# MCU.net
KiCad netlist of a schematic drawn in Altium Designer
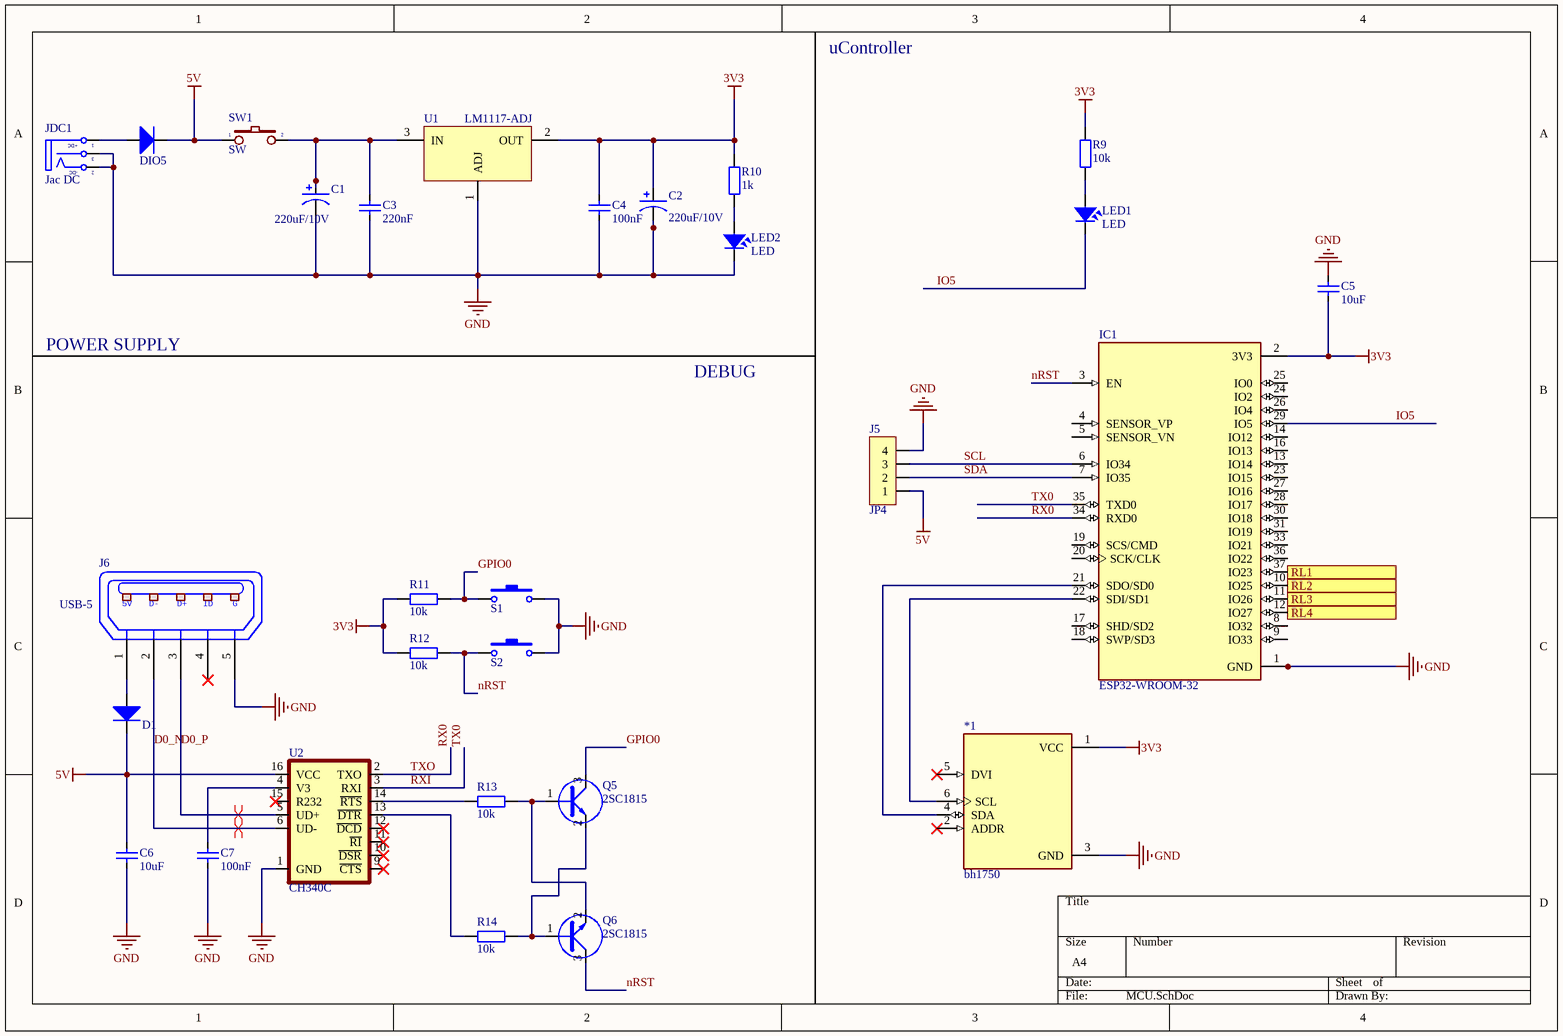
[diagram p0: MCU.SchDoc]

(export (version "E")
  (design (tool "Eeschema 10.0.6"))
  (components
    (comp (ref "*1") (value "bh1750") (footprint "BH1750") (libsource (lib "Main") (part "bh1750")))
    (comp (ref "C1")
      (value "220uF/10V")
      (footprint "C5mm")
      (description "Polarized Capacitor (Axial)")
      (fields (field (name "PUBLISHER") "Altium Limited"))
      (libsource (lib "Ven_lib") (part "Cap Pol"))
    )
    (comp (ref "C2")
      (value "220uF/10V")
      (footprint "C5mm")
      (description "Polarized Capacitor (Axial)")
      (fields (field (name "PUBLISHER") "Altium Limited"))
      (libsource (lib "Ven_lib") (part "Cap Pol"))
    )
    (comp (ref "C3")
      (value "220nF")
      (footprint "CAP_0805")
      (description "Capacitor")
      (fields (field (name "PUBLISHER") "Altium Limited"))
      (libsource (lib "My Library") (part "CapSMD"))
    )
    (comp (ref "C4")
      (value "100nF")
      (footprint "CAP_0805")
      (description "Capacitor")
      (fields (field (name "PUBLISHER") "Altium Limited"))
      (libsource (lib "My Library") (part "CapSMD"))
    )
    (comp (ref "C5")
      (value "10uF")
      (footprint "CAP_0805")
      (description "Capacitor")
      (fields (field (name "PUBLISHER") "Altium Limited"))
      (libsource (lib "My Library") (part "CapSMD"))
    )
    (comp (ref "C6")
      (value "10uF")
      (footprint "CAP_0805")
      (description "Capacitor")
      (fields (field (name "PUBLISHER") "Altium Limited"))
      (libsource (lib "My Library") (part "CapSMD"))
    )
    (comp (ref "C7")
      (value "100nF")
      (footprint "CAP_0805")
      (description "Capacitor")
      (fields (field (name "PUBLISHER") "Altium Limited"))
      (libsource (lib "My Library") (part "CapSMD"))
    )
    (comp (ref "D1")
      (value "Diode SMD")
      (footprint "DIO-214AC(SMA)")
      (description "Default Diode")
      (fields (field (name "PUBLISHER") "Altium Limited"))
      (libsource (lib "My Library") (part "Diode SMD"))
    )
    (comp (ref "DIO5")
      (value "Diode SMD")
      (footprint "DIO-214AC(SMA)")
      (description "Default Diode")
      (fields (field (name "PUBLISHER") "Altium Limited"))
      (libsource (lib "My Library") (part "Diode SMD"))
    )
    (comp (ref "IC1")
      (value "ESP32-WROOM-32")
      (footprint "MODULE_ESP32-WROOM-32")
      (description "Bluetooth, WiFi Transceiver Module 2.4GHz ~ 2.5GHz Surface Mount")
      (fields (field (name "MF") "Espressif Systems") (field (name "DIGI-KEY_PART_NUMBER") "1904-1010-1-ND"))
      (libsource (lib "Ven_lib") (part "ESP32-WROOM-32"))
    )
    (comp (ref "J5")
      (value "JP4")
      (footprint "JP4-C1T")
      (description "WR-PHD 2.54 mm Angled Socket Header")
      (fields
        (field (name "MANUFACTURER") "Würth Elektronik eiSos GmbH")
        (field (name "PARTNO") "613004143121")
        (field (name "CREATED BY") "Karrer Zheng")
      )
      (libsource (lib "My Library") (part "JP4"))
    )
    (comp (ref "J6")
      (value "USB-5")
      (footprint "USB-M1")
      (fields
        (field (name "MANUFACTURER") "FCI")
        (field (name "MANUFACTURER PART NUMBER") "10118193-0001LF")
        (field (name ".CREATOR") "MM")
        (field (name ".CHECKED PCB") "RF")
        (field (name ".CHECKED SCH") "MM")
      )
      (libsource (lib "My Library") (part "USB-5"))
    )
    (comp (ref "JDC1")
      (value "Jac DC")
      (footprint "DC-IN")
      (description "Jac DC input")
      (libsource (lib "My Library") (part "DCIN"))
    )
    (comp (ref "LED1")
      (value "LED")
      (footprint "LED-0805-Orange")
      (description "LED Single colour Green and Red")
      (libsource (lib "My Library") (part "LED"))
    )
    (comp (ref "LED2")
      (value "LED")
      (footprint "LED-0805-Red")
      (description "LED Single colour Green and Red")
      (libsource (lib "My Library") (part "LED"))
    )
    (comp (ref "Q5")
      (value "2SC1815")
      (footprint "SOT23D")
      (description "NPN 600mW, ECB")
      (libsource (lib "My Library") (part "C1815"))
    )
    (comp (ref "Q6")
      (value "2SC1815")
      (footprint "SOT23D")
      (description "NPN 600mW, ECB")
      (libsource (lib "") (part "C1815_1"))
    )
    (comp (ref "R9")
      (value "10k")
      (footprint "RES-SMD-0805")
      (description "Resistor SMD")
      (fields
        (field (name "MANUFACTURER") "Generic Components")
        (field (name "PUBLISHER") "Altium Hobart Technology Centre")
      )
      (libsource (lib "My Library") (part "Resistor - SMD"))
    )
    (comp (ref "R10")
      (value "1k")
      (footprint "RES-SMD-0805")
      (description "Resistor SMD")
      (fields
        (field (name "MANUFACTURER") "Generic Components")
        (field (name "PUBLISHER") "Altium Hobart Technology Centre")
      )
      (libsource (lib "My Library") (part "Resistor - SMD"))
    )
    (comp (ref "R11")
      (value "10k")
      (footprint "RES-SMD-0805")
      (description "Resistor SMD")
      (fields
        (field (name "MANUFACTURER") "Generic Components")
        (field (name "PUBLISHER") "Altium Hobart Technology Centre")
      )
      (libsource (lib "My Library") (part "Resistor - SMD"))
    )
    (comp (ref "R12")
      (value "10k")
      (footprint "RES-SMD-0805")
      (description "Resistor SMD")
      (fields
        (field (name "MANUFACTURER") "Generic Components")
        (field (name "PUBLISHER") "Altium Hobart Technology Centre")
      )
      (libsource (lib "My Library") (part "Resistor - SMD"))
    )
    (comp (ref "R13")
      (value "10k")
      (footprint "RES-SMD-0805")
      (description "Resistor SMD")
      (fields
        (field (name "MANUFACTURER") "Generic Components")
        (field (name "PUBLISHER") "Altium Hobart Technology Centre")
      )
      (libsource (lib "My Library") (part "Resistor - SMD"))
    )
    (comp (ref "R14")
      (value "10k")
      (footprint "RES-SMD-0805")
      (description "Resistor SMD")
      (fields
        (field (name "MANUFACTURER") "Generic Components")
        (field (name "PUBLISHER") "Altium Hobart Technology Centre")
      )
      (libsource (lib "My Library") (part "Resistor - SMD"))
    )
    (comp (ref "S1")
      (value "SW-SMD")
      (footprint "SW 3x2x4")
      (description "Switch")
      (fields (field (name "PUBLISHER") "Altium Limited"))
      (libsource (lib "My Library") (part "SW-SMD"))
    )
    (comp (ref "S2")
      (value "SW-SMD")
      (footprint "SW 3x2x4")
      (description "Switch")
      (fields (field (name "PUBLISHER") "Altium Limited"))
      (libsource (lib "My Library") (part "SW-SMD"))
    )
    (comp (ref "SW1")
      (value "SW")
      (footprint "SW2")
      (description "Switch button 2 pin")
      (libsource (lib "My Library") (part "SW2"))
    )
    (comp (ref "U1")
      (value "LM1117-ADJ")
      (footprint "LM1117-SOP")
      (description "800mA Low-Dropout Linear Regulator")
      (fields (field (name "CREATOR") "Nguyen Ba Bien"))
      (libsource (lib "My Library") (part "LM1117-ADJ"))
    )
    (comp (ref "U2")
      (value "CH340C")
      (footprint "SOP-16")
      (description "USB to serial chip CH340")
      (fields (field (name "MF") "WCH"))
      (libsource (lib "My Library") (part "CH340C"))
    )
  )
  (nets
    (net (code "1") (name "/D0_N") (class "Default")
      (node (ref "J6") (pin "2") (pinfunction "P2_2") (pintype "passive"))
      (node (ref "U2") (pin "6") (pinfunction "UD-_6") (pintype "bidirectional"))
    )
    (net (code "2") (name "/D0_P") (class "Default")
      (node (ref "J6") (pin "3") (pinfunction "P3_3") (pintype "passive"))
      (node (ref "U2") (pin "5") (pinfunction "UD+_5") (pintype "bidirectional"))
    )
    (net (code "3") (name "/GPIO0") (class "Default")
      (node (ref "Q5") (pin "3") (pinfunction "C_3") (pintype "passive"))
      (node (ref "R11") (pin "1") (pinfunction "1_1") (pintype "passive"))
      (node (ref "S1") (pin "1") (pinfunction "1_1") (pintype "passive"))
    )
    (net (code "4") (name "/IO5") (class "Default")
      (node (ref "IC1") (pin "29") (pinfunction "IO5_29") (pintype "bidirectional"))
      (node (ref "LED1") (pin "2") (pinfunction "2_2") (pintype "passive"))
    )
    (net (code "5") (name "/RL1") (class "Default")
      (node (ref "IC1") (pin "37") (pinfunction "IO23_37") (pintype "bidirectional"))
    )
    (net (code "6") (name "/RL2") (class "Default")
      (node (ref "IC1") (pin "10") (pinfunction "IO25_10") (pintype "bidirectional"))
    )
    (net (code "7") (name "/RL3") (class "Default")
      (node (ref "IC1") (pin "11") (pinfunction "IO26_11") (pintype "bidirectional"))
    )
    (net (code "8") (name "/RL4") (class "Default")
      (node (ref "IC1") (pin "12") (pinfunction "IO27_12") (pintype "bidirectional"))
    )
    (net (code "9") (name "/RX0") (class "Default")
      (node (ref "IC1") (pin "34") (pinfunction "RXD0_34") (pintype "bidirectional"))
      (node (ref "U2") (pin "2") (pinfunction "TXO_2") (pintype "bidirectional"))
    )
    (net (code "10") (name "/RXI") (class "Default")
      (node (ref "IC1") (pin "35") (pinfunction "TXD0_35") (pintype "bidirectional"))
      (node (ref "U2") (pin "3") (pinfunction "RXI_3") (pintype "bidirectional"))
    )
    (net (code "11") (name "/SCL") (class "Default")
      (node (ref "IC1") (pin "6") (pinfunction "IO34_6") (pintype "input"))
      (node (ref "J5") (pin "3") (pinfunction "3_3") (pintype "passive"))
    )
    (net (code "12") (name "/SDA") (class "Default")
      (node (ref "IC1") (pin "7") (pinfunction "IO35_7") (pintype "input"))
      (node (ref "J5") (pin "2") (pinfunction "2_2") (pintype "passive"))
    )
    (net (code "13") (name "/nRST") (class "Default")
      (node (ref "IC1") (pin "3") (pinfunction "EN_3") (pintype "input"))
      (node (ref "Q6") (pin "3") (pinfunction "C_3") (pintype "passive"))
      (node (ref "R12") (pin "1") (pinfunction "1_1") (pintype "passive"))
      (node (ref "S2") (pin "1") (pinfunction "1_1") (pintype "passive"))
    )
    (net (code "14") (name "3V3") (class "Default")
      (node (ref "*1") (pin "1") (pinfunction "VCC_1") (pintype "power_in"))
      (node (ref "C2") (pin "1") (pinfunction "1_1") (pintype "passive"))
      (node (ref "C4") (pin "2") (pinfunction "2_2") (pintype "passive"))
      (node (ref "C5") (pin "2") (pinfunction "2_2") (pintype "passive"))
      (node (ref "IC1") (pin "2") (pinfunction "3V3_2") (pintype "power_in"))
      (node (ref "R10") (pin "1") (pinfunction "1_1") (pintype "passive"))
      (node (ref "R11") (pin "2") (pinfunction "2_2") (pintype "passive"))
      (node (ref "R12") (pin "2") (pinfunction "2_2") (pintype "passive"))
      (node (ref "R9") (pin "1") (pinfunction "1_1") (pintype "passive"))
      (node (ref "U1") (pin "2") (pinfunction "OUT_2") (pintype "passive"))
    )
    (net (code "15") (name "5V") (class "Default")
      (node (ref "C6") (pin "2") (pinfunction "2_2") (pintype "passive"))
      (node (ref "D1") (pin "2") (pinfunction "K_2") (pintype "passive"))
      (node (ref "DIO5") (pin "2") (pinfunction "K_2") (pintype "passive"))
      (node (ref "J5") (pin "1") (pinfunction "1_1") (pintype "passive"))
      (node (ref "SW1") (pin "1") (pinfunction "1_1") (pintype "passive"))
      (node (ref "U2") (pin "16") (pinfunction "VCC_16") (pintype "bidirectional"))
    )
    (net (code "16") (name "GND") (class "Default")
      (node (ref "*1") (pin "3") (pinfunction "GND_3") (pintype "power_in"))
      (node (ref "C1") (pin "2") (pinfunction "2_2") (pintype "passive"))
      (node (ref "C2") (pin "2") (pinfunction "2_2") (pintype "passive"))
      (node (ref "C3") (pin "1") (pinfunction "1_1") (pintype "passive"))
      (node (ref "C4") (pin "1") (pinfunction "1_1") (pintype "passive"))
      (node (ref "C5") (pin "1") (pinfunction "1_1") (pintype "passive"))
      (node (ref "C6") (pin "1") (pinfunction "1_1") (pintype "passive"))
      (node (ref "C7") (pin "1") (pinfunction "1_1") (pintype "passive"))
      (node (ref "IC1") (pin "1") (pinfunction "GND_1") (pintype "power_in"))
      (node (ref "IC1") (pin "15") (pinfunction "GND_15") (pintype "power_in"))
      (node (ref "IC1") (pin "38") (pinfunction "GND_38") (pintype "power_in"))
      (node (ref "IC1") (pin "39_1") (pinfunction "GND_39_1") (pintype "power_in"))
      (node (ref "IC1") (pin "39_10") (pinfunction "GND_39_10") (pintype "power_in"))
      (node (ref "IC1") (pin "39_11") (pinfunction "GND_39_11") (pintype "power_in"))
      (node (ref "IC1") (pin "39_12") (pinfunction "GND_39_12") (pintype "power_in"))
      (node (ref "IC1") (pin "39_13") (pinfunction "GND_39_13") (pintype "power_in"))
      (node (ref "IC1") (pin "39_14") (pinfunction "GND_39_14") (pintype "power_in"))
      (node (ref "IC1") (pin "39_15") (pinfunction "GND_39_15") (pintype "power_in"))
      (node (ref "IC1") (pin "39_16") (pinfunction "GND_39_16") (pintype "power_in"))
      (node (ref "IC1") (pin "39_17") (pinfunction "GND_39_17") (pintype "power_in"))
      (node (ref "IC1") (pin "39_18") (pinfunction "GND_39_18") (pintype "power_in"))
      (node (ref "IC1") (pin "39_19") (pinfunction "GND_39_19") (pintype "power_in"))
      (node (ref "IC1") (pin "39_2") (pinfunction "GND_39_2") (pintype "power_in"))
      (node (ref "IC1") (pin "39_20") (pinfunction "GND_39_20") (pintype "power_in"))
      (node (ref "IC1") (pin "39_21") (pinfunction "GND_39_21") (pintype "power_in"))
      (node (ref "IC1") (pin "39_3") (pinfunction "GND_39_3") (pintype "power_in"))
      (node (ref "IC1") (pin "39_4") (pinfunction "GND_39_4") (pintype "power_in"))
      (node (ref "IC1") (pin "39_5") (pinfunction "GND_39_5") (pintype "power_in"))
      (node (ref "IC1") (pin "39_6") (pinfunction "GND_39_6") (pintype "power_in"))
      (node (ref "IC1") (pin "39_7") (pinfunction "GND_39_7") (pintype "power_in"))
      (node (ref "IC1") (pin "39_8") (pinfunction "GND_39_8") (pintype "power_in"))
      (node (ref "IC1") (pin "39_9") (pinfunction "GND_39_9") (pintype "power_in"))
      (node (ref "J5") (pin "4") (pinfunction "4_4") (pintype "passive"))
      (node (ref "J6") (pin "5") (pinfunction "P5_5") (pintype "passive"))
      (node (ref "JDC1") (pin "2") (pinfunction "TN_2") (pintype "passive"))
      (node (ref "JDC1") (pin "3") (pinfunction "S_3") (pintype "power_in"))
      (node (ref "LED2") (pin "2") (pinfunction "2_2") (pintype "passive"))
      (node (ref "S1") (pin "2") (pinfunction "2_2") (pintype "passive"))
      (node (ref "S2") (pin "2") (pinfunction "2_2") (pintype "passive"))
      (node (ref "U1") (pin "1") (pinfunction "ADJ_1") (pintype "passive"))
      (node (ref "U2") (pin "1") (pinfunction "GND_1") (pintype "bidirectional"))
    )
    (net (code "17") (name "Net-(*1-SCL)") (class "Default")
      (node (ref "*1") (pin "6") (pinfunction "SCL_6") (pintype "input"))
      (node (ref "IC1") (pin "22") (pinfunction "SDI/SD1_22") (pintype "bidirectional"))
    )
    (net (code "18") (name "Net-(*1-SDA)") (class "Default")
      (node (ref "*1") (pin "4") (pinfunction "SDA_4") (pintype "bidirectional"))
      (node (ref "IC1") (pin "21") (pinfunction "SDO/SD0_21") (pintype "bidirectional"))
    )
    (net (code "19") (name "Net-(D1-A)") (class "Default")
      (node (ref "D1") (pin "1") (pinfunction "A_1") (pintype "passive"))
      (node (ref "J6") (pin "1") (pinfunction "P1_1") (pintype "passive"))
    )
    (net (code "20") (name "Net-(DIO5-A)") (class "Default")
      (node (ref "DIO5") (pin "1") (pinfunction "A_1") (pintype "passive"))
      (node (ref "JDC1") (pin "1") (pinfunction "T_1") (pintype "passive"))
    )
    (net (code "21") (name "Net-(LED1-Pad1)") (class "Default")
      (node (ref "LED1") (pin "1") (pinfunction "1_1") (pintype "passive"))
      (node (ref "R9") (pin "2") (pinfunction "2_2") (pintype "passive"))
    )
    (net (code "22") (name "Net-(LED2-Pad1)") (class "Default")
      (node (ref "LED2") (pin "1") (pinfunction "1_1") (pintype "passive"))
      (node (ref "R10") (pin "2") (pinfunction "2_2") (pintype "passive"))
    )
    (net (code "23") (name "Net-(Q5-B)") (class "Default")
      (node (ref "Q5") (pin "1") (pinfunction "B_1") (pintype "passive"))
      (node (ref "Q6") (pin "2") (pinfunction "E_2") (pintype "passive"))
      (node (ref "R13") (pin "1") (pinfunction "1_1") (pintype "passive"))
    )
    (net (code "24") (name "Net-(Q5-E)") (class "Default")
      (node (ref "Q5") (pin "2") (pinfunction "E_2") (pintype "passive"))
      (node (ref "Q6") (pin "1") (pinfunction "B_1") (pintype "passive"))
      (node (ref "R14") (pin "1") (pinfunction "1_1") (pintype "passive"))
    )
    (net (code "25") (name "Net-(U1-IN)") (class "Default")
      (node (ref "C1") (pin "1") (pinfunction "1_1") (pintype "passive"))
      (node (ref "C3") (pin "2") (pinfunction "2_2") (pintype "passive"))
      (node (ref "SW1") (pin "2") (pinfunction "2_2") (pintype "passive"))
      (node (ref "U1") (pin "3") (pinfunction "IN_3") (pintype "passive"))
    )
    (net (code "26") (name "Net-(U2-V3)") (class "Default")
      (node (ref "C7") (pin "2") (pinfunction "2_2") (pintype "passive"))
      (node (ref "U2") (pin "4") (pinfunction "V3_4") (pintype "bidirectional"))
    )
    (net (code "27") (name "Net-(U2-~{DTR})") (class "Default")
      (node (ref "R14") (pin "2") (pinfunction "2_2") (pintype "passive"))
      (node (ref "U2") (pin "13") (pinfunction "~{DTR}_13") (pintype "bidirectional"))
    )
    (net (code "28") (name "Net-(U2-~{RTS})") (class "Default")
      (node (ref "R13") (pin "2") (pinfunction "2_2") (pintype "passive"))
      (node (ref "U2") (pin "14") (pinfunction "~{RTS}_14") (pintype "bidirectional"))
    )
    (net (code "29") (name "unconnected-(*1-ADDR-Pad2)") (class "Default")
      (node (ref "*1") (pin "2") (pinfunction "ADDR_2") (pintype "input+no_connect"))
    )
    (net (code "30") (name "unconnected-(*1-DVI-Pad5)") (class "Default")
      (node (ref "*1") (pin "5") (pinfunction "DVI_5") (pintype "input+no_connect"))
    )
    (net (code "31") (name "unconnected-(IC1-IO0-Pad25)") (class "Default")
      (node (ref "IC1") (pin "25") (pinfunction "IO0_25") (pintype "bidirectional"))
    )
    (net (code "32") (name "unconnected-(IC1-IO2-Pad24)") (class "Default")
      (node (ref "IC1") (pin "24") (pinfunction "IO2_24") (pintype "bidirectional"))
    )
    (net (code "33") (name "unconnected-(IC1-IO4-Pad26)") (class "Default")
      (node (ref "IC1") (pin "26") (pinfunction "IO4_26") (pintype "bidirectional"))
    )
    (net (code "34") (name "unconnected-(IC1-IO12-Pad14)") (class "Default")
      (node (ref "IC1") (pin "14") (pinfunction "IO12_14") (pintype "bidirectional"))
    )
    (net (code "35") (name "unconnected-(IC1-IO13-Pad16)") (class "Default")
      (node (ref "IC1") (pin "16") (pinfunction "IO13_16") (pintype "bidirectional"))
    )
    (net (code "36") (name "unconnected-(IC1-IO14-Pad13)") (class "Default")
      (node (ref "IC1") (pin "13") (pinfunction "IO14_13") (pintype "bidirectional"))
    )
    (net (code "37") (name "unconnected-(IC1-IO15-Pad23)") (class "Default")
      (node (ref "IC1") (pin "23") (pinfunction "IO15_23") (pintype "bidirectional"))
    )
    (net (code "38") (name "unconnected-(IC1-IO16-Pad27)") (class "Default")
      (node (ref "IC1") (pin "27") (pinfunction "IO16_27") (pintype "bidirectional"))
    )
    (net (code "39") (name "unconnected-(IC1-IO17-Pad28)") (class "Default")
      (node (ref "IC1") (pin "28") (pinfunction "IO17_28") (pintype "bidirectional"))
    )
    (net (code "40") (name "unconnected-(IC1-IO18-Pad30)") (class "Default")
      (node (ref "IC1") (pin "30") (pinfunction "IO18_30") (pintype "bidirectional"))
    )
    (net (code "41") (name "unconnected-(IC1-IO19-Pad31)") (class "Default")
      (node (ref "IC1") (pin "31") (pinfunction "IO19_31") (pintype "bidirectional"))
    )
    (net (code "42") (name "unconnected-(IC1-IO21-Pad33)") (class "Default")
      (node (ref "IC1") (pin "33") (pinfunction "IO21_33") (pintype "bidirectional"))
    )
    (net (code "43") (name "unconnected-(IC1-IO22-Pad36)") (class "Default")
      (node (ref "IC1") (pin "36") (pinfunction "IO22_36") (pintype "bidirectional"))
    )
    (net (code "44") (name "unconnected-(IC1-IO32-Pad8)") (class "Default")
      (node (ref "IC1") (pin "8") (pinfunction "IO32_8") (pintype "bidirectional"))
    )
    (net (code "45") (name "unconnected-(IC1-IO33-Pad9)") (class "Default")
      (node (ref "IC1") (pin "9") (pinfunction "IO33_9") (pintype "bidirectional"))
    )
    (net (code "46") (name "unconnected-(IC1-SCK{slash}CLK-Pad20)") (class "Default")
      (node (ref "IC1") (pin "20") (pinfunction "SCK/CLK_20") (pintype "bidirectional"))
    )
    (net (code "47") (name "unconnected-(IC1-SCS{slash}CMD-Pad19)") (class "Default")
      (node (ref "IC1") (pin "19") (pinfunction "SCS/CMD_19") (pintype "bidirectional"))
    )
    (net (code "48") (name "unconnected-(IC1-SENSOR_VN-Pad5)") (class "Default")
      (node (ref "IC1") (pin "5") (pinfunction "SENSOR_VN_5") (pintype "input"))
    )
    (net (code "49") (name "unconnected-(IC1-SENSOR_VP-Pad4)") (class "Default")
      (node (ref "IC1") (pin "4") (pinfunction "SENSOR_VP_4") (pintype "input"))
    )
    (net (code "50") (name "unconnected-(IC1-SHD{slash}SD2-Pad17)") (class "Default")
      (node (ref "IC1") (pin "17") (pinfunction "SHD/SD2_17") (pintype "bidirectional"))
    )
    (net (code "51") (name "unconnected-(IC1-SWP{slash}SD3-Pad18)") (class "Default")
      (node (ref "IC1") (pin "18") (pinfunction "SWP/SD3_18") (pintype "bidirectional"))
    )
    (net (code "52") (name "unconnected-(J6-P4-Pad4)") (class "Default")
      (node (ref "J6") (pin "4") (pinfunction "P4_4") (pintype "passive+no_connect"))
    )
    (net (code "53") (name "unconnected-(U2-R232-Pad15)") (class "Default")
      (node (ref "U2") (pin "15") (pinfunction "R232_15") (pintype "bidirectional+no_connect"))
    )
    (net (code "54") (name "unconnected-(U2-~{CTS}-Pad9)") (class "Default")
      (node (ref "U2") (pin "9") (pinfunction "~{CTS}_9") (pintype "bidirectional+no_connect"))
    )
    (net (code "55") (name "unconnected-(U2-~{DCD}-Pad12)") (class "Default")
      (node (ref "U2") (pin "12") (pinfunction "~{DCD}_12") (pintype "bidirectional+no_connect"))
    )
    (net (code "56") (name "unconnected-(U2-~{DSR}-Pad10)") (class "Default")
      (node (ref "U2") (pin "10") (pinfunction "~{DSR}_10") (pintype "bidirectional+no_connect"))
    )
    (net (code "57") (name "unconnected-(U2-~{RI}-Pad11)") (class "Default")
      (node (ref "U2") (pin "11") (pinfunction "~{RI}_11") (pintype "bidirectional+no_connect"))
    )
  )
)
